# IntelliServo.net
KiCad netlist of a schematic drawn in EAGLE
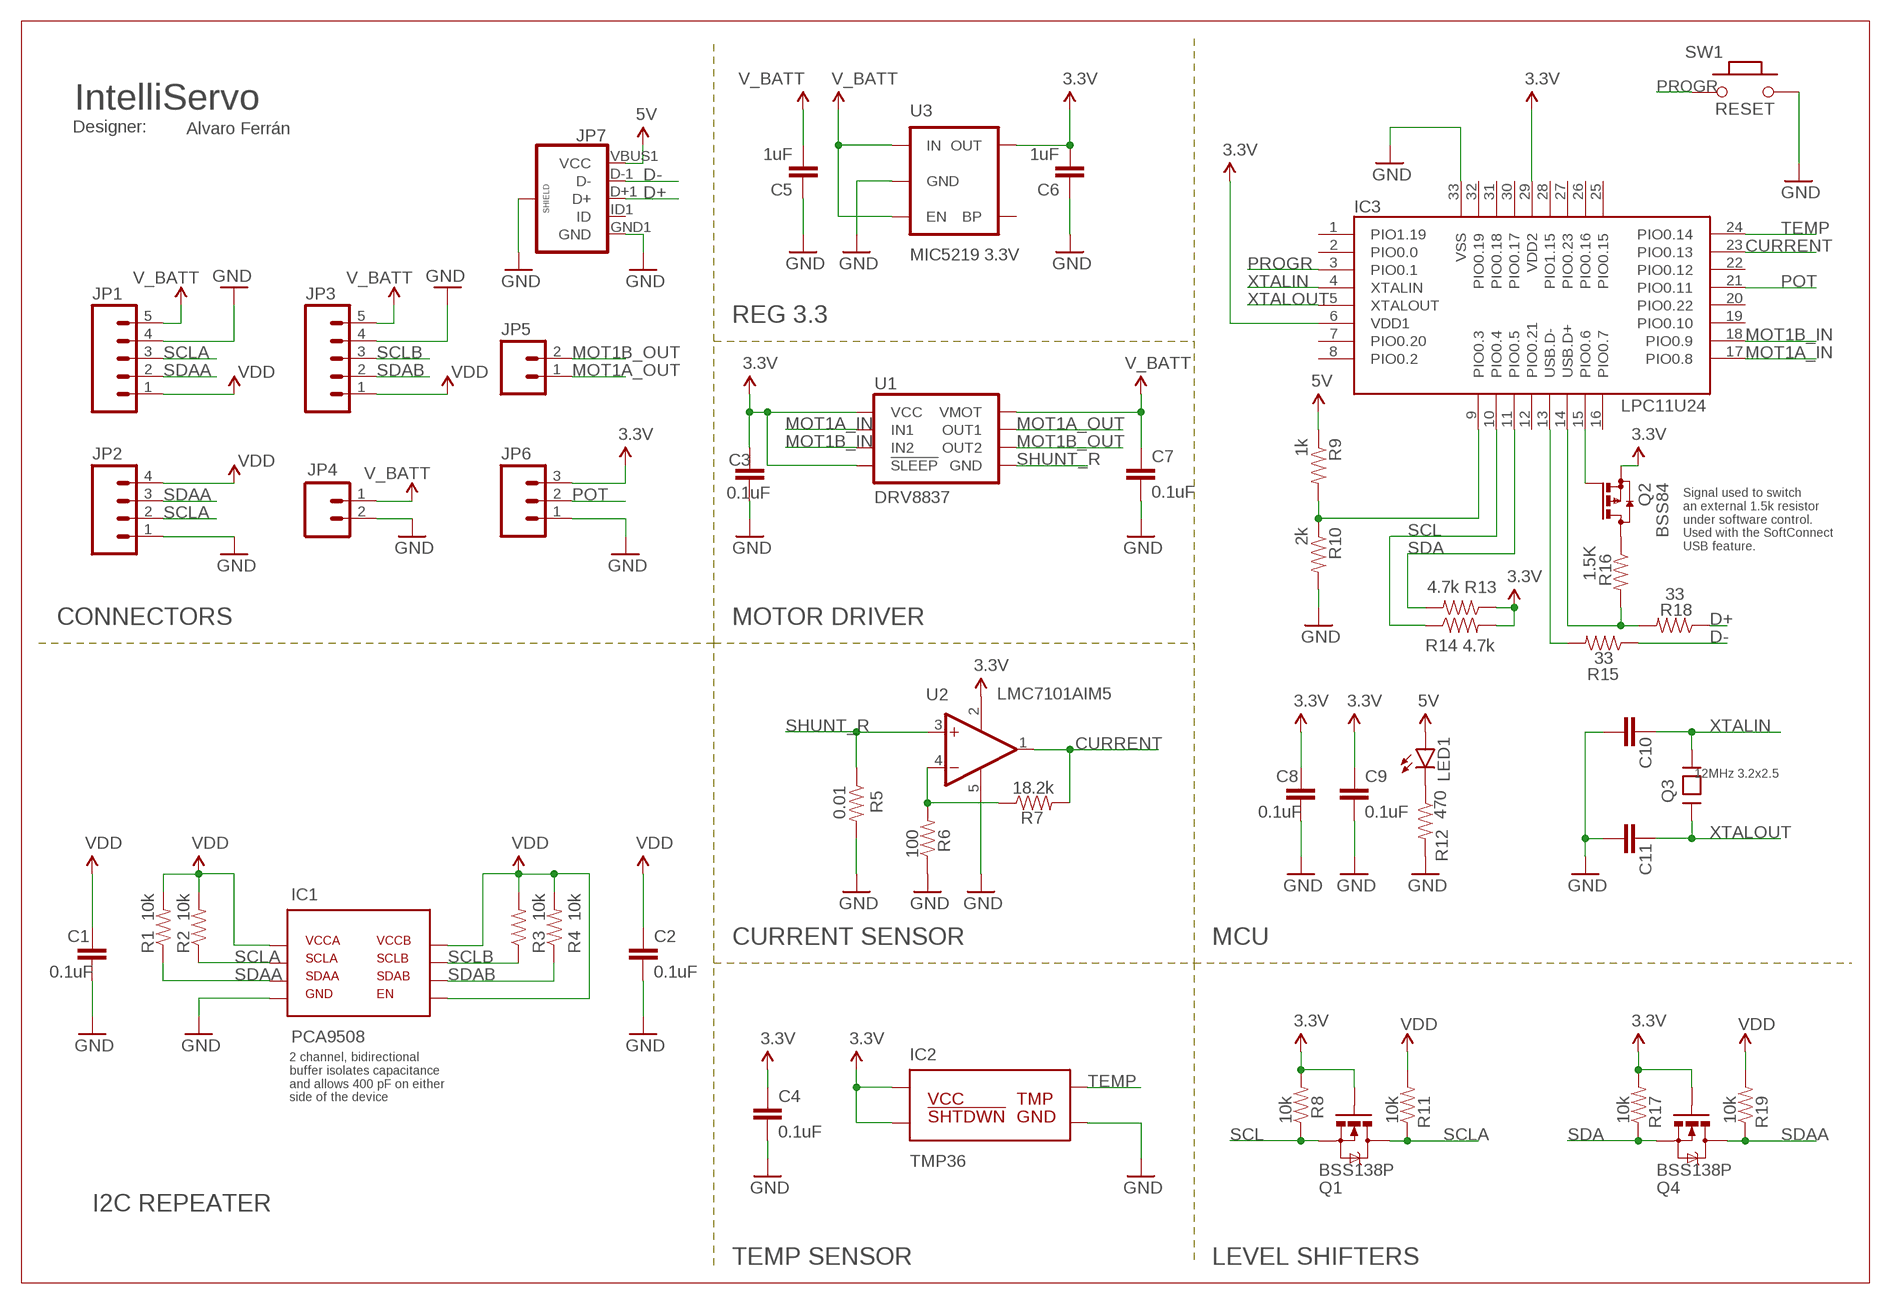
[diagram p0: schematic, sheet 1]

(export (version "E")
  (design (tool "Eeschema 10.0.6"))
  (components
    (comp (ref "C1")
      (value "0.1uF")
      (footprint "eagle-import:0402-CAP")
      (libsource (lib "eagle-import") (part "CAP0402-CAP"))
    )
    (comp (ref "C2")
      (value "0.1uF")
      (footprint "eagle-import:0402-CAP")
      (libsource (lib "eagle-import") (part "CAP0402-CAP"))
    )
    (comp (ref "C3")
      (value "0.1uF")
      (footprint "eagle-import:0402-CAP")
      (libsource (lib "eagle-import") (part "0.1UF-16V(+-10%)(0402)"))
    )
    (comp (ref "C4")
      (value "0.1uF")
      (footprint "eagle-import:0402-CAP")
      (libsource (lib "eagle-import") (part "CAP0402-CAP"))
    )
    (comp (ref "C5")
      (value "1uF")
      (footprint "eagle-import:0402-CAP")
      (libsource (lib "eagle-import") (part "CAP0402-CAP"))
    )
    (comp (ref "C6")
      (value "1uF")
      (footprint "eagle-import:0402-CAP")
      (libsource (lib "eagle-import") (part "CAP0402-CAP"))
    )
    (comp (ref "C7")
      (value "0.1uF")
      (footprint "eagle-import:0402-CAP")
      (libsource (lib "eagle-import") (part "0.1UF-16V(+-10%)(0402)"))
    )
    (comp (ref "C8")
      (value "0.1uF")
      (footprint "eagle-import:0402-CAP")
      (libsource (lib "eagle-import") (part "CAP0402-CAP"))
    )
    (comp (ref "C9")
      (value "0.1uF")
      (footprint "eagle-import:0402-CAP")
      (libsource (lib "eagle-import") (part "CAP0402-CAP"))
    )
    (comp (ref "C10")
      (value "27pF")
      (footprint "eagle-import:0402-CAP")
      (libsource (lib "eagle-import") (part "CAP0402-CAP"))
    )
    (comp (ref "C11")
      (value "27pF")
      (footprint "eagle-import:0402-CAP")
      (libsource (lib "eagle-import") (part "CAP0402-CAP"))
    )
    (comp (ref "IC1")
      (value "PCA9508")
      (footprint "eagle-import:TSSOP8")
      (libsource (lib "eagle-import") (part "PCA9508"))
    )
    (comp (ref "IC2")
      (value "TMP36")
      (footprint "eagle-import:SOT23-5")
      (libsource (lib "eagle-import") (part "TMP36"))
    )
    (comp (ref "IC3")
      (value "LPC11U24")
      (footprint "eagle-import:HVQFN33_5X5MM")
      (libsource (lib "eagle-import") (part "LPC11U2X_HVQFN33(5X5)"))
    )
    (comp (ref "JP1")
      (value "M05LOCK")
      (footprint "eagle-import:1X05_LOCK")
      (libsource (lib "eagle-import") (part "M05LOCK"))
    )
    (comp (ref "JP2")
      (value "M04LOCK")
      (footprint "eagle-import:1X04_LOCK")
      (libsource (lib "eagle-import") (part "M04LOCK"))
    )
    (comp (ref "JP3")
      (value "M05LOCK")
      (footprint "eagle-import:1X05_LOCK")
      (libsource (lib "eagle-import") (part "M05LOCK"))
    )
    (comp (ref "JP4")
      (value "M02LOCK")
      (footprint "eagle-import:1X02_LOCK")
      (libsource (lib "eagle-import") (part "M02LOCK"))
    )
    (comp (ref "JP5")
      (value "M02LOCK")
      (footprint "eagle-import:1X02_LOCK")
      (libsource (lib "eagle-import") (part "M02LOCK"))
    )
    (comp (ref "JP6")
      (value "M03LOCK")
      (footprint "eagle-import:1X03_LOCK")
      (libsource (lib "eagle-import") (part "M03LOCK"))
    )
    (comp (ref "JP7")
      (value "USB_MICROB")
      (footprint "eagle-import:USB-B-MICRO-SMD_V03")
      (libsource (lib "eagle-import") (part "USB_MICROB_PLUGCONN-11752"))
    )
    (comp (ref "LED1")
      (value "LED0603")
      (footprint "eagle-import:LED-0603")
      (libsource (lib "eagle-import") (part "LED0603"))
    )
    (comp (ref "Q1")
      (value "BSS138P")
      (footprint "eagle-import:SOT23-3")
      (libsource (lib "eagle-import") (part "MOSFET-NCHANNELBSS138"))
    )
    (comp (ref "Q2")
      (value "BSS84")
      (footprint "eagle-import:SOT23")
      (libsource (lib "eagle-import") (part "BSS84"))
    )
    (comp (ref "Q3")
      (value "12MHz 3.2x2.5")
      (footprint "eagle-import:CRYSTAL_3.2X2.5")
      (libsource (lib "eagle-import") (part "CRYSTAL3.2X2.5"))
    )
    (comp (ref "Q4")
      (value "BSS138P")
      (footprint "eagle-import:SOT23-3")
      (libsource (lib "eagle-import") (part "MOSFET-NCHANNELBSS138"))
    )
    (comp (ref "R1")
      (value "10k")
      (footprint "eagle-import:0402-RES")
      (libsource (lib "eagle-import") (part "RESISTOR0402-RES"))
    )
    (comp (ref "R2")
      (value "10k")
      (footprint "eagle-import:0402-RES")
      (libsource (lib "eagle-import") (part "RESISTOR0402-RES"))
    )
    (comp (ref "R3")
      (value "10k")
      (footprint "eagle-import:0402-RES")
      (libsource (lib "eagle-import") (part "RESISTOR0402-RES"))
    )
    (comp (ref "R4")
      (value "10k")
      (footprint "eagle-import:0402-RES")
      (libsource (lib "eagle-import") (part "RESISTOR0402-RES"))
    )
    (comp (ref "R5")
      (value "0.01")
      (footprint "eagle-import:0805")
      (libsource (lib "eagle-import") (part "RESISTOR0805-RES"))
    )
    (comp (ref "R6")
      (value "100")
      (footprint "eagle-import:0402-RES")
      (libsource (lib "eagle-import") (part "RESISTOR0402-RES"))
    )
    (comp (ref "R7")
      (value "18.2k")
      (footprint "eagle-import:0402-RES")
      (libsource (lib "eagle-import") (part "RESISTOR0402-RES"))
    )
    (comp (ref "R8")
      (value "10k")
      (footprint "eagle-import:0402-RES")
      (libsource (lib "eagle-import") (part "RESISTOR0402-RES"))
    )
    (comp (ref "R9")
      (value "1k")
      (footprint "eagle-import:0402-RES")
      (libsource (lib "eagle-import") (part "RESISTOR0402-RES"))
    )
    (comp (ref "R10")
      (value "2k")
      (footprint "eagle-import:0402-RES")
      (libsource (lib "eagle-import") (part "RESISTOR0402-RES"))
    )
    (comp (ref "R11")
      (value "10k")
      (footprint "eagle-import:0402-RES")
      (libsource (lib "eagle-import") (part "RESISTOR0402-RES"))
    )
    (comp (ref "R12")
      (value "470")
      (footprint "eagle-import:0402-RES")
      (libsource (lib "eagle-import") (part "RESISTOR0402-RES"))
    )
    (comp (ref "R13")
      (value "4.7k")
      (footprint "eagle-import:0402-RES")
      (libsource (lib "eagle-import") (part "RESISTOR0402-RES"))
    )
    (comp (ref "R14")
      (value "4.7k")
      (footprint "eagle-import:0402-RES")
      (libsource (lib "eagle-import") (part "RESISTOR0402-RES"))
    )
    (comp (ref "R15")
      (value "33")
      (footprint "eagle-import:0402-RES")
      (libsource (lib "eagle-import") (part "RESISTOR0402-RES"))
    )
    (comp (ref "R16")
      (value "1.5K")
      (footprint "eagle-import:0402-RES")
      (libsource (lib "eagle-import") (part "RESISTOR0402-RES"))
    )
    (comp (ref "R17")
      (value "10k")
      (footprint "eagle-import:0402-RES")
      (libsource (lib "eagle-import") (part "RESISTOR0402-RES"))
    )
    (comp (ref "R18")
      (value "33")
      (footprint "eagle-import:0402-RES")
      (libsource (lib "eagle-import") (part "RESISTOR0402-RES"))
    )
    (comp (ref "R19")
      (value "10k")
      (footprint "eagle-import:0402-RES")
      (libsource (lib "eagle-import") (part "RESISTOR0402-RES"))
    )
    (comp (ref "SW1")
      (value "RESET")
      (footprint "eagle-import:157SW")
      (libsource (lib "eagle-import") (part "PB157"))
    )
    (comp (ref "U1")
      (value "DRV8837")
      (footprint "eagle-import:DSG")
      (libsource (lib "eagle-import") (part "DRV8837"))
    )
    (comp (ref "U2")
      (value "LMC7101AIM5")
      (footprint "eagle-import:SOT23-5")
      (libsource (lib "eagle-import") (part "LMC7101AIM5"))
    )
    (comp (ref "U3")
      (value "MIC5219 3.3V")
      (footprint "eagle-import:SOT23-5")
      (libsource (lib "eagle-import") (part "V_REG_MIC52193.3V"))
    )
  )
  (nets
    (net (code "1") (name "/CURRENT") (class "Default")
      (node (ref "IC3") (pin "23") (pinfunction "PIO0.13_23") (pintype "bidirectional"))
      (node (ref "R7") (pin "2") (pinfunction "2_2") (pintype "passive"))
      (node (ref "U2") (pin "1") (pinfunction "OUT_1") (pintype "output"))
    )
    (net (code "2") (name "/D+") (class "Default")
      (node (ref "JP7") (pin "D+1") (pinfunction "D+_D+1") (pintype "bidirectional"))
      (node (ref "R18") (pin "1") (pinfunction "1_1") (pintype "passive"))
    )
    (net (code "3") (name "/D-") (class "Default")
      (node (ref "JP7") (pin "D-1") (pinfunction "D-_D-1") (pintype "bidirectional"))
      (node (ref "R15") (pin "1") (pinfunction "1_1") (pintype "passive"))
    )
    (net (code "4") (name "/MOT1A_IN") (class "Default")
      (node (ref "IC3") (pin "17") (pinfunction "PIO0.8_17") (pintype "bidirectional"))
      (node (ref "U1") (pin "6") (pinfunction "IN1_6") (pintype "bidirectional"))
    )
    (net (code "5") (name "/MOT1A_OUT") (class "Default")
      (node (ref "JP5") (pin "1") (pinfunction "1_1") (pintype "passive"))
      (node (ref "U1") (pin "2") (pinfunction "OUT1_2") (pintype "bidirectional"))
    )
    (net (code "6") (name "/MOT1B_IN") (class "Default")
      (node (ref "IC3") (pin "18") (pinfunction "PIO0.9_18") (pintype "bidirectional"))
      (node (ref "U1") (pin "5") (pinfunction "IN2_5") (pintype "bidirectional"))
    )
    (net (code "7") (name "/MOT1B_OUT") (class "Default")
      (node (ref "JP5") (pin "2") (pinfunction "2_2") (pintype "passive"))
      (node (ref "U1") (pin "3") (pinfunction "OUT2_3") (pintype "bidirectional"))
    )
    (net (code "8") (name "/POT") (class "Default")
      (node (ref "IC3") (pin "21") (pinfunction "PIO0.11_21") (pintype "bidirectional"))
      (node (ref "JP6") (pin "2") (pinfunction "2_2") (pintype "passive"))
    )
    (net (code "9") (name "/PROGR") (class "Default")
      (node (ref "IC3") (pin "3") (pinfunction "PIO0.1_3") (pintype "bidirectional"))
      (node (ref "SW1") (pin "1") (pinfunction "1_1") (pintype "passive"))
    )
    (net (code "10") (name "/SCL") (class "Default")
      (node (ref "IC3") (pin "10") (pinfunction "PIO0.4_10") (pintype "bidirectional"))
      (node (ref "Q1") (pin "2") (pinfunction "S_2") (pintype "passive"))
      (node (ref "R14") (pin "1") (pinfunction "1_1") (pintype "passive"))
      (node (ref "R8") (pin "1") (pinfunction "1_1") (pintype "passive"))
    )
    (net (code "11") (name "/SCLA") (class "Default")
      (node (ref "IC1") (pin "2") (pinfunction "SCLA_2") (pintype "bidirectional"))
      (node (ref "JP1") (pin "3") (pinfunction "3_3") (pintype "passive"))
      (node (ref "JP2") (pin "2") (pinfunction "2_2") (pintype "passive"))
      (node (ref "Q1") (pin "3") (pinfunction "D_3") (pintype "passive"))
      (node (ref "R11") (pin "1") (pinfunction "1_1") (pintype "passive"))
      (node (ref "R2") (pin "1") (pinfunction "1_1") (pintype "passive"))
    )
    (net (code "12") (name "/SCLB") (class "Default")
      (node (ref "IC1") (pin "7") (pinfunction "SCLB_7") (pintype "bidirectional"))
      (node (ref "JP3") (pin "3") (pinfunction "3_3") (pintype "passive"))
      (node (ref "R3") (pin "1") (pinfunction "1_1") (pintype "passive"))
    )
    (net (code "13") (name "/SDA") (class "Default")
      (node (ref "IC3") (pin "11") (pinfunction "PIO0.5_11") (pintype "bidirectional"))
      (node (ref "Q4") (pin "2") (pinfunction "S_2") (pintype "passive"))
      (node (ref "R13") (pin "2") (pinfunction "2_2") (pintype "passive"))
      (node (ref "R17") (pin "1") (pinfunction "1_1") (pintype "passive"))
    )
    (net (code "14") (name "/SDAA") (class "Default")
      (node (ref "IC1") (pin "3") (pinfunction "SDAA_3") (pintype "bidirectional"))
      (node (ref "JP1") (pin "2") (pinfunction "2_2") (pintype "passive"))
      (node (ref "JP2") (pin "3") (pinfunction "3_3") (pintype "passive"))
      (node (ref "Q4") (pin "3") (pinfunction "D_3") (pintype "passive"))
      (node (ref "R1") (pin "1") (pinfunction "1_1") (pintype "passive"))
      (node (ref "R19") (pin "1") (pinfunction "1_1") (pintype "passive"))
    )
    (net (code "15") (name "/SDAB") (class "Default")
      (node (ref "IC1") (pin "6") (pinfunction "SDAB_6") (pintype "bidirectional"))
      (node (ref "JP3") (pin "2") (pinfunction "2_2") (pintype "passive"))
      (node (ref "R4") (pin "1") (pinfunction "1_1") (pintype "passive"))
    )
    (net (code "16") (name "/SHUNT_R") (class "Default")
      (node (ref "R5") (pin "1") (pinfunction "1_1") (pintype "passive"))
      (node (ref "U1") (pin "4") (pinfunction "GND_4") (pintype "bidirectional"))
      (node (ref "U1") (pin "PAD") (pinfunction "GND_PAD") (pintype "bidirectional"))
      (node (ref "U2") (pin "3") (pinfunction "+IN_3") (pintype "input"))
    )
    (net (code "17") (name "/TEMP") (class "Default")
      (node (ref "IC2") (pin "1") (pinfunction "TMP_1") (pintype "bidirectional"))
      (node (ref "IC3") (pin "24") (pinfunction "PIO0.14_24") (pintype "bidirectional"))
    )
    (net (code "18") (name "/XTALIN") (class "Default")
      (node (ref "C10") (pin "1") (pinfunction "1_1") (pintype "passive"))
      (node (ref "IC3") (pin "4") (pinfunction "XTALIN_4") (pintype "bidirectional"))
      (node (ref "Q3") (pin "3") (pinfunction "P$2_3") (pintype "passive"))
    )
    (net (code "19") (name "/XTALOUT") (class "Default")
      (node (ref "C11") (pin "1") (pinfunction "1_1") (pintype "passive"))
      (node (ref "IC3") (pin "5") (pinfunction "XTALOUT_5") (pintype "bidirectional"))
      (node (ref "Q3") (pin "1") (pinfunction "P$1_1") (pintype "passive"))
    )
    (net (code "20") (name "3.3V") (class "Default")
      (node (ref "C3") (pin "1") (pinfunction "1_1") (pintype "passive"))
      (node (ref "C4") (pin "1") (pinfunction "1_1") (pintype "passive"))
      (node (ref "C6") (pin "2") (pinfunction "2_2") (pintype "passive"))
      (node (ref "C8") (pin "1") (pinfunction "1_1") (pintype "passive"))
      (node (ref "C9") (pin "1") (pinfunction "1_1") (pintype "passive"))
      (node (ref "IC2") (pin "2") (pinfunction "VCC_2") (pintype "bidirectional"))
      (node (ref "IC2") (pin "4") (pinfunction "~{SHTDWN}_4") (pintype "bidirectional"))
      (node (ref "IC3") (pin "29") (pinfunction "VDD2_29") (pintype "bidirectional"))
      (node (ref "IC3") (pin "6") (pinfunction "VDD1_6") (pintype "bidirectional"))
      (node (ref "JP6") (pin "3") (pinfunction "3_3") (pintype "passive"))
      (node (ref "Q1") (pin "1") (pinfunction "G_1") (pintype "passive"))
      (node (ref "Q2") (pin "2") (pinfunction "S_2") (pintype "passive"))
      (node (ref "Q4") (pin "1") (pinfunction "G_1") (pintype "passive"))
      (node (ref "R13") (pin "1") (pinfunction "1_1") (pintype "passive"))
      (node (ref "R14") (pin "2") (pinfunction "2_2") (pintype "passive"))
      (node (ref "R17") (pin "2") (pinfunction "2_2") (pintype "passive"))
      (node (ref "R8") (pin "2") (pinfunction "2_2") (pintype "passive"))
      (node (ref "U1") (pin "7") (pinfunction "~{SLEEP}_7") (pintype "bidirectional"))
      (node (ref "U1") (pin "8") (pinfunction "VCC_8") (pintype "bidirectional"))
      (node (ref "U2") (pin "2") (pinfunction "V+_2") (pintype "power_in"))
      (node (ref "U3") (pin "5") (pinfunction "OUT_5") (pintype "passive"))
    )
    (net (code "21") (name "5V") (class "Default")
      (node (ref "JP7") (pin "VBUS1") (pinfunction "VCC_VBUS1") (pintype "bidirectional"))
      (node (ref "LED1") (pin "A") (pinfunction "A_A") (pintype "passive"))
      (node (ref "R9") (pin "1") (pinfunction "1_1") (pintype "passive"))
    )
    (net (code "22") (name "GND") (class "Default")
      (node (ref "C1") (pin "2") (pinfunction "2_2") (pintype "passive"))
      (node (ref "C10") (pin "2") (pinfunction "2_2") (pintype "passive"))
      (node (ref "C11") (pin "2") (pinfunction "2_2") (pintype "passive"))
      (node (ref "C2") (pin "2") (pinfunction "2_2") (pintype "passive"))
      (node (ref "C3") (pin "2") (pinfunction "2_2") (pintype "passive"))
      (node (ref "C4") (pin "2") (pinfunction "2_2") (pintype "passive"))
      (node (ref "C5") (pin "1") (pinfunction "1_1") (pintype "passive"))
      (node (ref "C6") (pin "1") (pinfunction "1_1") (pintype "passive"))
      (node (ref "C7") (pin "2") (pinfunction "2_2") (pintype "passive"))
      (node (ref "C8") (pin "2") (pinfunction "2_2") (pintype "passive"))
      (node (ref "C9") (pin "2") (pinfunction "2_2") (pintype "passive"))
      (node (ref "IC1") (pin "4") (pinfunction "GND_4") (pintype "bidirectional"))
      (node (ref "IC2") (pin "5") (pinfunction "GND_5") (pintype "bidirectional"))
      (node (ref "IC3") (pin "33") (pinfunction "VSS_33") (pintype "bidirectional"))
      (node (ref "JP1") (pin "4") (pinfunction "4_4") (pintype "passive"))
      (node (ref "JP2") (pin "1") (pinfunction "1_1") (pintype "passive"))
      (node (ref "JP3") (pin "4") (pinfunction "4_4") (pintype "passive"))
      (node (ref "JP4") (pin "2") (pinfunction "2_2") (pintype "passive"))
      (node (ref "JP6") (pin "1") (pinfunction "1_1") (pintype "passive"))
      (node (ref "JP7") (pin "GND1") (pinfunction "GND_GND1") (pintype "bidirectional"))
      (node (ref "JP7") (pin "SHIELD1") (pinfunction "SHIELD_SHIELD1") (pintype "bidirectional"))
      (node (ref "JP7") (pin "SHIELD2") (pinfunction "SHIELD_SHIELD2") (pintype "bidirectional"))
      (node (ref "JP7") (pin "SHIELD3") (pinfunction "SHIELD_SHIELD3") (pintype "bidirectional"))
      (node (ref "R10") (pin "2") (pinfunction "2_2") (pintype "passive"))
      (node (ref "R12") (pin "2") (pinfunction "2_2") (pintype "passive"))
      (node (ref "R5") (pin "2") (pinfunction "2_2") (pintype "passive"))
      (node (ref "R6") (pin "1") (pinfunction "1_1") (pintype "passive"))
      (node (ref "SW1") (pin "2") (pinfunction "2_2") (pintype "passive"))
      (node (ref "U2") (pin "5") (pinfunction "V-_5") (pintype "power_in"))
      (node (ref "U3") (pin "2") (pinfunction "GND_2") (pintype "input"))
    )
    (net (code "23") (name "Net-(IC3-PIO0.3)") (class "Default")
      (node (ref "IC3") (pin "9") (pinfunction "PIO0.3_9") (pintype "bidirectional"))
      (node (ref "R10") (pin "1") (pinfunction "1_1") (pintype "passive"))
      (node (ref "R9") (pin "2") (pinfunction "2_2") (pintype "passive"))
    )
    (net (code "24") (name "Net-(IC3-PIO0.6)") (class "Default")
      (node (ref "IC3") (pin "15") (pinfunction "PIO0.6_15") (pintype "bidirectional"))
      (node (ref "Q2") (pin "1") (pinfunction "G_1") (pintype "passive"))
    )
    (net (code "25") (name "Net-(IC3-USB.D+)") (class "Default")
      (node (ref "IC3") (pin "14") (pinfunction "USB.D+_14") (pintype "bidirectional"))
      (node (ref "R16") (pin "2") (pinfunction "2_2") (pintype "passive"))
      (node (ref "R18") (pin "2") (pinfunction "2_2") (pintype "passive"))
    )
    (net (code "26") (name "Net-(IC3-USB.D-)") (class "Default")
      (node (ref "IC3") (pin "13") (pinfunction "USB.D-_13") (pintype "bidirectional"))
      (node (ref "R15") (pin "2") (pinfunction "2_2") (pintype "passive"))
    )
    (net (code "27") (name "Net-(LED1-PadC)") (class "Default")
      (node (ref "LED1") (pin "C") (pinfunction "C_C") (pintype "passive"))
      (node (ref "R12") (pin "1") (pinfunction "1_1") (pintype "passive"))
    )
    (net (code "28") (name "Net-(Q2-D)") (class "Default")
      (node (ref "Q2") (pin "3") (pinfunction "D_3") (pintype "passive"))
      (node (ref "R16") (pin "1") (pinfunction "1_1") (pintype "passive"))
    )
    (net (code "29") (name "Net-(U2--IN)") (class "Default")
      (node (ref "R6") (pin "2") (pinfunction "2_2") (pintype "passive"))
      (node (ref "R7") (pin "1") (pinfunction "1_1") (pintype "passive"))
      (node (ref "U2") (pin "4") (pinfunction "-IN_4") (pintype "input"))
    )
    (net (code "30") (name "VDD") (class "Default")
      (node (ref "C1") (pin "1") (pinfunction "1_1") (pintype "passive"))
      (node (ref "C2") (pin "1") (pinfunction "1_1") (pintype "passive"))
      (node (ref "IC1") (pin "1") (pinfunction "VCCA_1") (pintype "bidirectional"))
      (node (ref "IC1") (pin "5") (pinfunction "EN_5") (pintype "bidirectional"))
      (node (ref "IC1") (pin "8") (pinfunction "VCCB_8") (pintype "bidirectional"))
      (node (ref "JP1") (pin "1") (pinfunction "1_1") (pintype "passive"))
      (node (ref "JP2") (pin "4") (pinfunction "4_4") (pintype "passive"))
      (node (ref "JP3") (pin "1") (pinfunction "1_1") (pintype "passive"))
      (node (ref "R1") (pin "2") (pinfunction "2_2") (pintype "passive"))
      (node (ref "R11") (pin "2") (pinfunction "2_2") (pintype "passive"))
      (node (ref "R19") (pin "2") (pinfunction "2_2") (pintype "passive"))
      (node (ref "R2") (pin "2") (pinfunction "2_2") (pintype "passive"))
      (node (ref "R3") (pin "2") (pinfunction "2_2") (pintype "passive"))
      (node (ref "R4") (pin "2") (pinfunction "2_2") (pintype "passive"))
    )
    (net (code "31") (name "V_BATT") (class "Default")
      (node (ref "C5") (pin "2") (pinfunction "2_2") (pintype "passive"))
      (node (ref "C7") (pin "1") (pinfunction "1_1") (pintype "passive"))
      (node (ref "JP1") (pin "5") (pinfunction "5_5") (pintype "passive"))
      (node (ref "JP3") (pin "5") (pinfunction "5_5") (pintype "passive"))
      (node (ref "JP4") (pin "1") (pinfunction "1_1") (pintype "passive"))
      (node (ref "U1") (pin "1") (pinfunction "VMOT_1") (pintype "bidirectional"))
      (node (ref "U3") (pin "1") (pinfunction "IN_1") (pintype "input"))
      (node (ref "U3") (pin "3") (pinfunction "EN_3") (pintype "input"))
    )
    (net (code "32") (name "unconnected-(IC3-PIO0.0-Pad2)") (class "Default")
      (node (ref "IC3") (pin "2") (pinfunction "PIO0.0_2") (pintype "bidirectional"))
    )
    (net (code "33") (name "unconnected-(IC3-PIO0.2-Pad8)") (class "Default")
      (node (ref "IC3") (pin "8") (pinfunction "PIO0.2_8") (pintype "bidirectional"))
    )
    (net (code "34") (name "unconnected-(IC3-PIO0.7-Pad16)") (class "Default")
      (node (ref "IC3") (pin "16") (pinfunction "PIO0.7_16") (pintype "bidirectional"))
    )
    (net (code "35") (name "unconnected-(IC3-PIO0.10-Pad19)") (class "Default")
      (node (ref "IC3") (pin "19") (pinfunction "PIO0.10_19") (pintype "bidirectional"))
    )
    (net (code "36") (name "unconnected-(IC3-PIO0.12-Pad22)") (class "Default")
      (node (ref "IC3") (pin "22") (pinfunction "PIO0.12_22") (pintype "bidirectional"))
    )
    (net (code "37") (name "unconnected-(IC3-PIO0.15-Pad25)") (class "Default")
      (node (ref "IC3") (pin "25") (pinfunction "PIO0.15_25") (pintype "bidirectional"))
    )
    (net (code "38") (name "unconnected-(IC3-PIO0.16-Pad26)") (class "Default")
      (node (ref "IC3") (pin "26") (pinfunction "PIO0.16_26") (pintype "bidirectional"))
    )
    (net (code "39") (name "unconnected-(IC3-PIO0.17-Pad30)") (class "Default")
      (node (ref "IC3") (pin "30") (pinfunction "PIO0.17_30") (pintype "bidirectional"))
    )
    (net (code "40") (name "unconnected-(IC3-PIO0.18-Pad31)") (class "Default")
      (node (ref "IC3") (pin "31") (pinfunction "PIO0.18_31") (pintype "bidirectional"))
    )
    (net (code "41") (name "unconnected-(IC3-PIO0.19-Pad32)") (class "Default")
      (node (ref "IC3") (pin "32") (pinfunction "PIO0.19_32") (pintype "bidirectional"))
    )
    (net (code "42") (name "unconnected-(IC3-PIO0.20-Pad7)") (class "Default")
      (node (ref "IC3") (pin "7") (pinfunction "PIO0.20_7") (pintype "bidirectional"))
    )
    (net (code "43") (name "unconnected-(IC3-PIO0.21-Pad12)") (class "Default")
      (node (ref "IC3") (pin "12") (pinfunction "PIO0.21_12") (pintype "bidirectional"))
    )
    (net (code "44") (name "unconnected-(IC3-PIO0.22-Pad20)") (class "Default")
      (node (ref "IC3") (pin "20") (pinfunction "PIO0.22_20") (pintype "bidirectional"))
    )
    (net (code "45") (name "unconnected-(IC3-PIO0.23-Pad27)") (class "Default")
      (node (ref "IC3") (pin "27") (pinfunction "PIO0.23_27") (pintype "bidirectional"))
    )
    (net (code "46") (name "unconnected-(IC3-PIO1.15-Pad28)") (class "Default")
      (node (ref "IC3") (pin "28") (pinfunction "PIO1.15_28") (pintype "bidirectional"))
    )
    (net (code "47") (name "unconnected-(IC3-PIO1.19-Pad1)") (class "Default")
      (node (ref "IC3") (pin "1") (pinfunction "PIO1.19_1") (pintype "bidirectional"))
    )
    (net (code "48") (name "unconnected-(JP7-ID-PadID1)") (class "Default")
      (node (ref "JP7") (pin "ID1") (pinfunction "ID_ID1") (pintype "bidirectional"))
    )
    (net (code "49") (name "unconnected-(U3-BP-Pad4)") (class "Default")
      (node (ref "U3") (pin "4") (pinfunction "BP_4") (pintype "input"))
    )
  )
)
